# Sheet2.net
KiCad netlist of a schematic drawn in Altium Designer
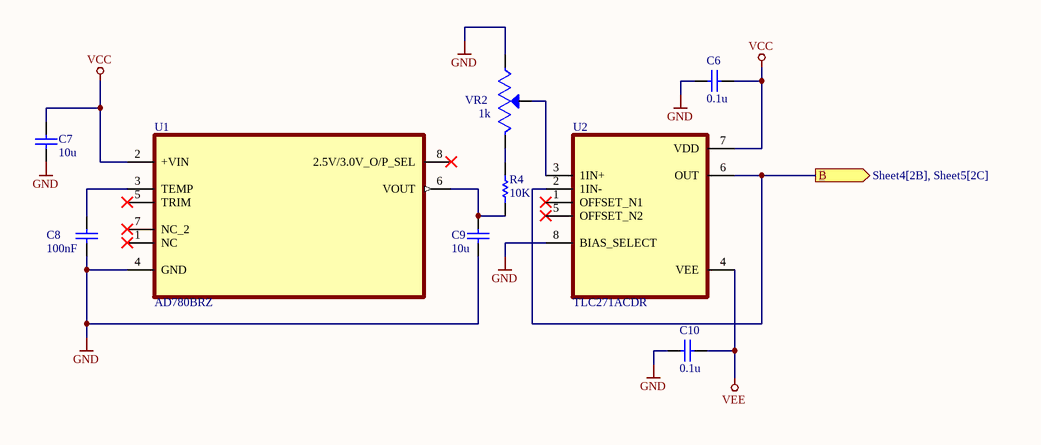
[diagram p0: Sheet2.SchDoc]

(export (version "E")
  (design (tool "Eeschema 10.0.6"))
  (components
    (comp (ref "C6")
      (value "0.1u")
      (footprint "CAPC2012X150N")
      (description "Capacitor")
      (libsource (lib "Simulation Generic Components") (part "Capacitor"))
    )
    (comp (ref "C7")
      (value "10u")
      (footprint "CAPC2012X150N")
      (description "Capacitor")
      (libsource (lib "Simulation Generic Components") (part "Capacitor"))
    )
    (comp (ref "C8")
      (value "100nF")
      (footprint "CAPC2012X150N")
      (description "Capacitor")
      (libsource (lib "Simulation Generic Components") (part "Capacitor"))
    )
    (comp (ref "C9")
      (value "10u")
      (footprint "CAPC2012X150N")
      (description "Capacitor")
      (libsource (lib "Simulation Generic Components") (part "Capacitor"))
    )
    (comp (ref "C10")
      (value "0.1u")
      (footprint "CAPC2012X150N")
      (description "Capacitor")
      (libsource (lib "Simulation Generic Components") (part "Capacitor"))
    )
    (comp (ref "R4")
      (value "10K")
      (footprint "RES_ERA6AHD330V")
      (description "Resistor")
      (libsource (lib "Simulation Generic Components") (part "Resistor"))
    )
    (comp (ref "U1")
      (value "AD780BRZ")
      (footprint "SOIC127P600X175-8N")
      (description "2.5 V/3.0 V High Precision Reference")
      (fields (field (name "MF") "Analog Devices"))
      (libsource (lib "AD780BRZ") (part "AD780BRZ"))
    )
    (comp (ref "U2")
      (value "TLC271ACDR")
      (footprint "SOIC127P599X175-8N")
      (description "Single, 16-V, 2-MHz, 5-mV offset voltage, In to V- operational amplifier")
      (fields (field (name "MF") "Texas Instruments"))
      (libsource (lib "TLC271ACDR") (part "TLC271ACDR"))
    )
    (comp (ref "VR2")
      (value "1k")
      (footprint "TRIM_3296W-1-103RLF")
      (description "Trimmer, Cermet, Rest 10 Kilohms, PCB, 25 Turns, Pwr-Rtg 0.5W ¦ Bourns 3296W-1-103RLF")
      (fields (field (name "MF") "Bourns") (field (name "MP") "3296W-1-103RLF"))
      (libsource (lib "3296W-1-103RLF") (part "3296W-1-103RLF"))
    )
  )
  (nets
    (net (code "1") (name "/B") (class "Default")
      (node (ref "U2") (pin "2") (pinfunction "1IN-_2") (pintype "passive"))
      (node (ref "U2") (pin "6") (pinfunction "OUT_6") (pintype "passive"))
    )
    (net (code "2") (name "GND") (class "Default")
      (node (ref "C10") (pin "2") (pinfunction "2_2") (pintype "passive"))
      (node (ref "C6") (pin "2") (pinfunction "2_2") (pintype "passive"))
      (node (ref "C7") (pin "1") (pinfunction "1_1") (pintype "passive"))
      (node (ref "C8") (pin "1") (pinfunction "1_1") (pintype "passive"))
      (node (ref "C9") (pin "1") (pinfunction "1_1") (pintype "passive"))
      (node (ref "U1") (pin "4") (pinfunction "GND_4") (pintype "passive"))
      (node (ref "U2") (pin "8") (pinfunction "BIAS_SELECT_8") (pintype "passive"))
      (node (ref "VR2") (pin "1") (pinfunction "CCW_1") (pintype "passive"))
    )
    (net (code "3") (name "Net-(U1-TEMP)") (class "Default")
      (node (ref "C8") (pin "2") (pinfunction "2_2") (pintype "passive"))
      (node (ref "U1") (pin "3") (pinfunction "TEMP_3") (pintype "passive"))
    )
    (net (code "4") (name "Net-(U1-VOUT)") (class "Default")
      (node (ref "C9") (pin "2") (pinfunction "2_2") (pintype "passive"))
      (node (ref "R4") (pin "1") (pinfunction "1_1") (pintype "passive"))
      (node (ref "U1") (pin "6") (pinfunction "VOUT_6") (pintype "output"))
    )
    (net (code "5") (name "Net-(U2-1IN+)") (class "Default")
      (node (ref "U2") (pin "3") (pinfunction "1IN+_3") (pintype "passive"))
      (node (ref "VR2") (pin "2") (pinfunction "WIPER_2") (pintype "passive"))
    )
    (net (code "6") (name "Net-(VR2-CW)") (class "Default")
      (node (ref "R4") (pin "2") (pinfunction "2_2") (pintype "passive"))
      (node (ref "VR2") (pin "3") (pinfunction "CW_3") (pintype "passive"))
    )
    (net (code "7") (name "VCC") (class "Default")
      (node (ref "C6") (pin "1") (pinfunction "1_1") (pintype "passive"))
      (node (ref "C7") (pin "2") (pinfunction "2_2") (pintype "passive"))
      (node (ref "U1") (pin "2") (pinfunction "+VIN_2") (pintype "power_in"))
      (node (ref "U2") (pin "7") (pinfunction "VDD_7") (pintype "power_in"))
    )
    (net (code "8") (name "VEE") (class "Default")
      (node (ref "C10") (pin "1") (pinfunction "1_1") (pintype "passive"))
      (node (ref "U2") (pin "4") (pinfunction "VEE_4") (pintype "power_in"))
    )
    (net (code "9") (name "unconnected-(U1-2.5V{slash}3.0V_O{slash}P_SEL-Pad8)") (class "Default")
      (node (ref "U1") (pin "8") (pinfunction "2.5V/3.0V_O/P_SEL_8") (pintype "passive+no_connect"))
    )
    (net (code "10") (name "unconnected-(U1-NC-Pad1)") (class "Default")
      (node (ref "U1") (pin "1") (pinfunction "NC_1") (pintype "passive+no_connect"))
    )
    (net (code "11") (name "unconnected-(U1-NC_2-Pad7)") (class "Default")
      (node (ref "U1") (pin "7") (pinfunction "NC_2_7") (pintype "passive+no_connect"))
    )
    (net (code "12") (name "unconnected-(U1-TRIM-Pad5)") (class "Default")
      (node (ref "U1") (pin "5") (pinfunction "TRIM_5") (pintype "passive+no_connect"))
    )
    (net (code "13") (name "unconnected-(U2-OFFSET_N1-Pad1)") (class "Default")
      (node (ref "U2") (pin "1") (pinfunction "OFFSET_N1_1") (pintype "passive+no_connect"))
    )
    (net (code "14") (name "unconnected-(U2-OFFSET_N2-Pad5)") (class "Default")
      (node (ref "U2") (pin "5") (pinfunction "OFFSET_N2_5") (pintype "passive+no_connect"))
    )
  )
)
